# Current_Measure.net
KiCad netlist of a schematic drawn in Altium Designer
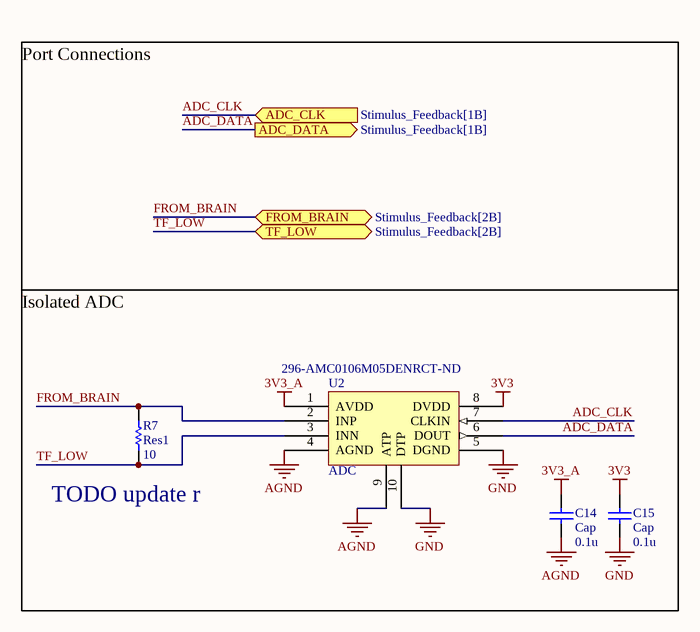
[diagram p0: Current_Measure.SchDoc]

(export (version "E")
  (design (tool "Eeschema 10.0.6"))
  (components
    (comp (ref "C14")
      (value "Cap")
      (footprint "CAPC1608X05N")
      (description "Capacitor")
      (fields (field (name "ALTIUM_VALUE") "0.1u") (field (name "PUBLISHER") "Altium Limited"))
      (libsource (lib "Miscellaneous Devices") (part "Cap"))
    )
    (comp (ref "C15")
      (value "Cap")
      (footprint "CAPC1608X05N")
      (description "Capacitor")
      (fields (field (name "ALTIUM_VALUE") "0.1u") (field (name "PUBLISHER") "Altium Limited"))
      (libsource (lib "Miscellaneous Devices") (part "Cap"))
    )
    (comp (ref "R7")
      (value "Res1")
      (footprint "0402_Res")
      (description "Resistor")
      (fields (field (name "ALTIUM_VALUE") "10") (field (name "PUBLISHER") "Altium Limited"))
      (libsource (lib "Miscellaneous Devices") (part "Res1"))
    )
    (comp (ref "U2")
      (value "ADC")
      (footprint "SON65P350X100_HS-9N")
      (fields (field (name "SUPPLIER PART NUMBER 1") "296-AMC0106M05DENRCT-ND"))
      (libsource (lib "Brain_Stim_Lib") (part "ADC"))
    )
  )
  (nets
    (net (code "1") (name "/ADC_CLK") (class "Default")
      (node (ref "U2") (pin "7") (pinfunction "CLKIN_7") (pintype "input"))
    )
    (net (code "2") (name "/ADC_DATA") (class "Default")
      (node (ref "U2") (pin "6") (pinfunction "DOUT_6") (pintype "output"))
    )
    (net (code "3") (name "/FROM_BRAIN") (class "Default")
      (node (ref "R7") (pin "1") (pinfunction "1_1") (pintype "passive"))
      (node (ref "U2") (pin "2") (pinfunction "INP_2") (pintype "passive"))
    )
    (net (code "4") (name "/TF_LOW") (class "Default")
      (node (ref "R7") (pin "2") (pinfunction "2_2") (pintype "passive"))
      (node (ref "U2") (pin "3") (pinfunction "INN_3") (pintype "passive"))
    )
    (net (code "5") (name "3V3") (class "Default")
      (node (ref "C15") (pin "2") (pinfunction "2_2") (pintype "passive"))
      (node (ref "U2") (pin "8") (pinfunction "DVDD_8") (pintype "passive"))
    )
    (net (code "6") (name "3V3_A") (class "Default")
      (node (ref "C14") (pin "2") (pinfunction "2_2") (pintype "passive"))
      (node (ref "U2") (pin "1") (pinfunction "AVDD_1") (pintype "passive"))
    )
    (net (code "7") (name "AGND") (class "Default")
      (node (ref "C14") (pin "1") (pinfunction "1_1") (pintype "passive"))
      (node (ref "U2") (pin "4") (pinfunction "AGND_4") (pintype "passive"))
      (node (ref "U2") (pin "9") (pinfunction "ATP_9") (pintype "passive"))
    )
    (net (code "8") (name "GND") (class "Default")
      (node (ref "C15") (pin "1") (pinfunction "1_1") (pintype "passive"))
      (node (ref "U2") (pin "10") (pinfunction "DTP_10") (pintype "passive"))
      (node (ref "U2") (pin "5") (pinfunction "DGND_5") (pintype "passive"))
    )
  )
)
